# FPGA_BANKS.net
KiCad netlist of a schematic drawn in Altium Designer
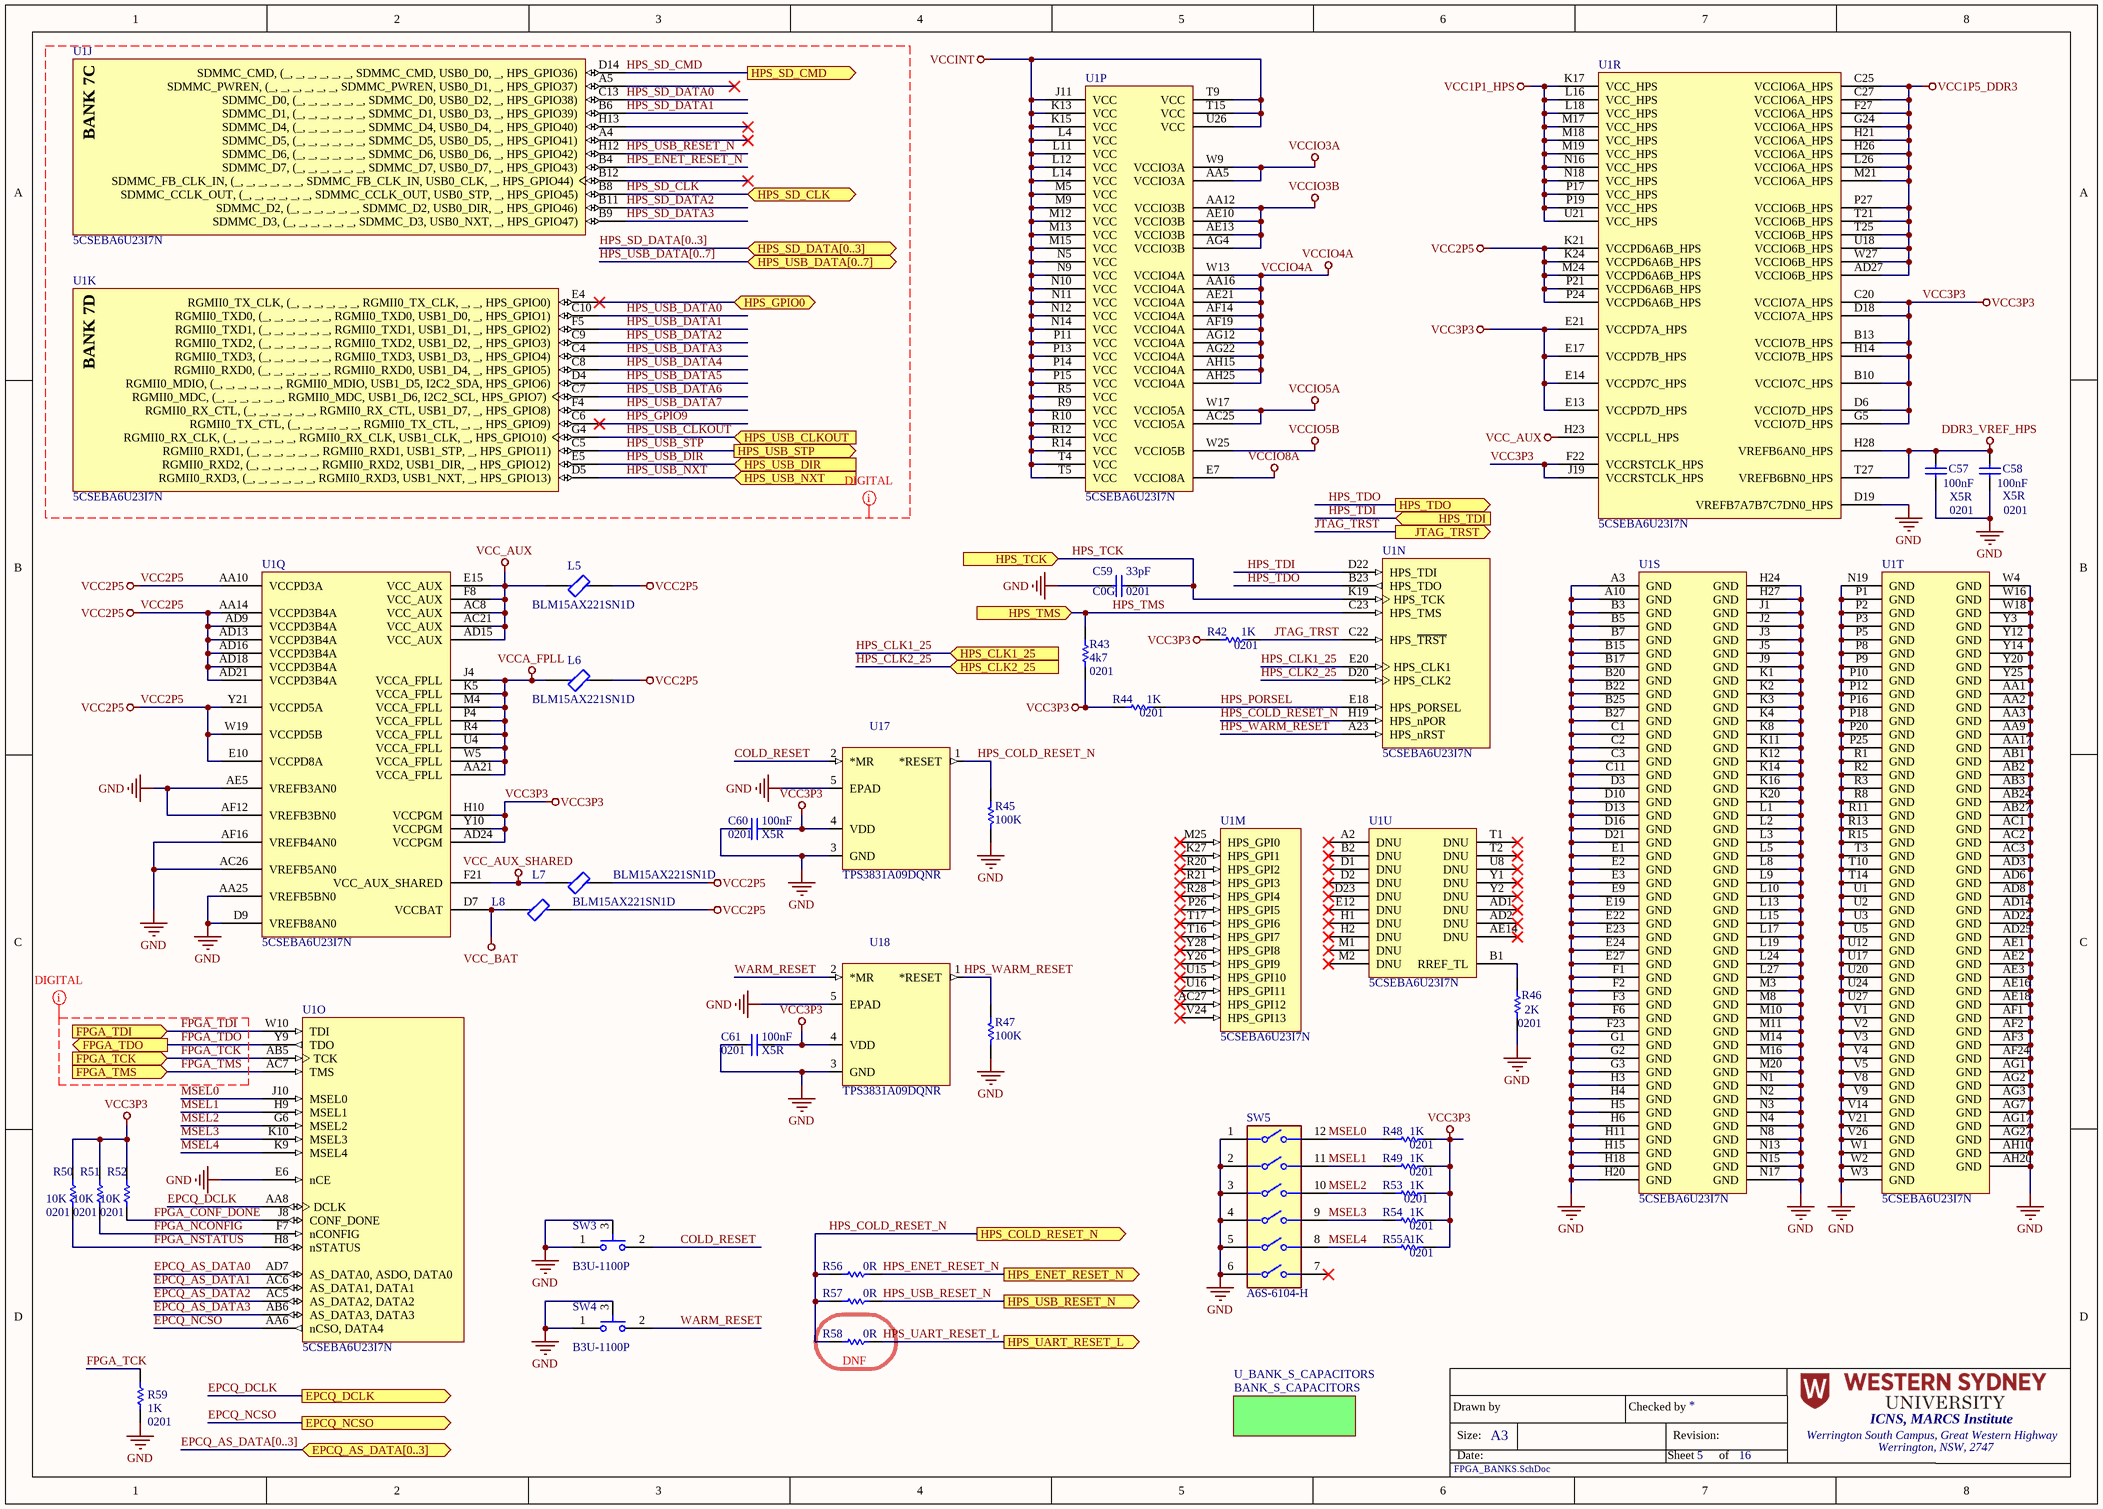
[diagram p0: FPGA_BANKS.SchDoc]

(export (version "E")
  (design (tool "Eeschema 10.0.6"))
  (components
    (comp (ref "C57")
      (value "CL03A104KP3NNNC")
      (footprint "CAP 0201 (0603)")
      (description "Cap Ceramic 0.1uF 10V X5R 10% Pad SMD 0201 85C T/R")
      (fields
        (field (name "TOLERANCE") "10%")
        (field (name "CAPACITANCE") "100nF")
        (field (name "MANUFACTURER") "Samsung")
        (field (name "CASE CODE (IMPERIAL)") "0201")
        (field (name "DIELECTRIC") "X5R")
        (field (name "SOURCE") "ICNS_PropheseeLib.SchLib")
      )
      (libsource (lib "Western Sydney University - ICNS") (part "CL03A104KP3NNNC"))
    )
    (comp (ref "C58")
      (value "CL03A104KP3NNNC")
      (footprint "CAP 0201 (0603)")
      (description "Cap Ceramic 0.1uF 10V X5R 10% Pad SMD 0201 85C T/R")
      (fields
        (field (name "TOLERANCE") "10%")
        (field (name "CAPACITANCE") "100nF")
        (field (name "MANUFACTURER") "Samsung")
        (field (name "CASE CODE (IMPERIAL)") "0201")
        (field (name "DIELECTRIC") "X5R")
        (field (name "SOURCE") "ICNS_PropheseeLib.SchLib")
      )
      (libsource (lib "Western Sydney University - ICNS") (part "CL03A104KP3NNNC"))
    )
    (comp (ref "C59")
      (value "CGA1A2C0G1E330J030BA")
      (footprint "CAP 0201 (0603)")
      (description "Cap Ceramic 33 pF 25V ±5% C0G, NP0 0201 (0603 Metric)")
      (fields
        (field (name "TOLERANCE") "5%")
        (field (name "MANUFACTURER") "TDK")
        (field (name "CAPACITANCE") "33pF")
        (field (name "CASE CODE (IMPERIAL)") "0201")
        (field (name "DIELECTRIC") "C0G")
        (field (name "SOURCE") "ICNS_PropheseeLib.SchLib")
      )
      (libsource (lib "Western Sydney University - ICNS") (part "CGA1A2C0G1E330J030BA"))
    )
    (comp (ref "C60")
      (value "CL03A104KP3NNNC")
      (footprint "CAP 0201 (0603)")
      (description "Cap Ceramic 0.1uF 10V X5R 10% Pad SMD 0201 85C T/R")
      (fields
        (field (name "TOLERANCE") "10%")
        (field (name "CAPACITANCE") "100nF")
        (field (name "MANUFACTURER") "Samsung")
        (field (name "CASE CODE (IMPERIAL)") "0201")
        (field (name "DIELECTRIC") "X5R")
        (field (name "SOURCE") "ICNS_PropheseeLib.SchLib")
      )
      (libsource (lib "Western Sydney University - ICNS") (part "CL03A104KP3NNNC"))
    )
    (comp (ref "C61")
      (value "CL03A104KP3NNNC")
      (footprint "CAP 0201 (0603)")
      (description "Cap Ceramic 0.1uF 10V X5R 10% Pad SMD 0201 85C T/R")
      (fields
        (field (name "TOLERANCE") "10%")
        (field (name "CAPACITANCE") "100nF")
        (field (name "MANUFACTURER") "Samsung")
        (field (name "CASE CODE (IMPERIAL)") "0201")
        (field (name "DIELECTRIC") "X5R")
        (field (name "SOURCE") "ICNS_PropheseeLib.SchLib")
      )
      (libsource (lib "Western Sydney University - ICNS") (part "CL03A104KP3NNNC"))
    )
    (comp (ref "L5")
      (value "BLM15AX221SN1D")
      (footprint "FP-BLM15-0_05-IPC_C")
      (description "Ferrite Bead Multi-Layer 220 Ohms @ 100 MHz 0402 (1005 Metric) 600mA 180mOhm")
      (fields
        (field (name "TOLERANCE") "25%")
        (field (name "MANUFACTURER") "Murata")
        (field (name "SOURCE") "ICNS_PropheseeLib.SchLib")
      )
      (libsource (lib "Western Sydney University - ICNS") (part "BLM15AX221SN1D"))
    )
    (comp (ref "L6")
      (value "BLM15AX221SN1D")
      (footprint "FP-BLM15-0_05-IPC_C")
      (description "Ferrite Bead Multi-Layer 220 Ohms @ 100 MHz 0402 (1005 Metric) 600mA 180mOhm")
      (fields
        (field (name "TOLERANCE") "25%")
        (field (name "MANUFACTURER") "Murata")
        (field (name "SOURCE") "ICNS_PropheseeLib.SchLib")
      )
      (libsource (lib "Western Sydney University - ICNS") (part "BLM15AX221SN1D"))
    )
    (comp (ref "L7")
      (value "BLM15AX221SN1D")
      (footprint "FP-BLM15-0_05-IPC_C")
      (description "Ferrite Bead Multi-Layer 220 Ohms @ 100 MHz 0402 (1005 Metric) 600mA 180mOhm")
      (fields
        (field (name "TOLERANCE") "25%")
        (field (name "MANUFACTURER") "Murata")
        (field (name "SOURCE") "ICNS_PropheseeLib.SchLib")
      )
      (libsource (lib "Western Sydney University - ICNS") (part "BLM15AX221SN1D"))
    )
    (comp (ref "L8")
      (value "BLM15AX221SN1D")
      (footprint "FP-BLM15-0_05-IPC_C")
      (description "Ferrite Bead Multi-Layer 220 Ohms @ 100 MHz 0402 (1005 Metric) 600mA 180mOhm")
      (fields
        (field (name "TOLERANCE") "25%")
        (field (name "MANUFACTURER") "Murata")
        (field (name "SOURCE") "ICNS_PropheseeLib.SchLib")
      )
      (libsource (lib "Western Sydney University - ICNS") (part "BLM15AX221SN1D"))
    )
    (comp (ref "R42")
      (value "1K")
      (footprint "RES 0201 (0603)")
      (description "Res Thick Film 0201 1K Ohm 1% 0.05W(1/20W) ±200ppm/C Pad SMD Automotive T/R")
      (fields
        (field (name "MANUFACTURER") "Yageo")
        (field (name "TOLERANCE") "1%")
        (field (name "CASE CODE (IMPERIAL)") "0201")
        (field (name "SOURCE") "ICNS_PropheseeLib.SchLib")
      )
      (libsource (lib "Western Sydney University - ICNS") (part "Symbol"))
    )
    (comp (ref "R43")
      (value "4k7")
      (footprint "RES 0201 (0603)")
      (description "Res Thick Film 0201 4.7K Ohm 1% 1/20W ±200ppm/°C Molded SMD Paper T/R")
      (fields
        (field (name "MANUFACTURER") "Yageo")
        (field (name "CASE CODE (IMPERIAL)") "0201")
        (field (name "MANUFACTURER PART NUMBER") "AC0201FR-074K7L")
        (field (name "SOURCE") "ICNS_PropheseeLib.SchLib")
      )
      (libsource (lib "Western Sydney University - ICNS") (part "Symbol"))
    )
    (comp (ref "R44")
      (value "1K")
      (footprint "RES 0201 (0603)")
      (description "Res Thick Film 0201 1K Ohm 1% 0.05W(1/20W) ±200ppm/C Pad SMD Automotive T/R")
      (fields
        (field (name "MANUFACTURER") "Yageo")
        (field (name "TOLERANCE") "1%")
        (field (name "CASE CODE (IMPERIAL)") "0201")
        (field (name "SOURCE") "ICNS_PropheseeLib.SchLib")
      )
      (libsource (lib "Western Sydney University - ICNS") (part "Symbol"))
    )
    (comp (ref "R45")
      (value "100K")
      (footprint "RES 0402 (1005)")
      (description "Res Thick Film 0402 100K Ohm 1% 0.2W(1/5W) ±100ppm/C Pad SMD Automotive T/R")
      (fields
        (field (name "TOLERANCE") "1%")
        (field (name "Comment") "CRCW0402100KFKEDHP")
        (field (name "SOURCE") "ICNS_PropheseeLib.SchLib")
      )
      (libsource (lib "Western Sydney University - ICNS") (part "Symbol"))
    )
    (comp (ref "R46")
      (value "2K")
      (footprint "RES 0201 (0603)")
      (description "Res Thick Film 0201 2K Ohm 1% 1/20W ±100ppm/°C Molded SMD SMD Paper T/R")
      (fields
        (field (name "MANUFACTURER") "Vishay Dale")
        (field (name "CASE CODE (IMPERIAL)") "0201")
        (field (name "MANUFACTURER PART NUMBER") "CRCW02012K00FKED")
        (field (name "SOURCE") "ICNS_PropheseeLib.SchLib")
      )
      (libsource (lib "Western Sydney University - ICNS") (part "CRCW02012K00FKED"))
    )
    (comp (ref "R47")
      (value "100K")
      (footprint "RES 0402 (1005)")
      (description "Res Thick Film 0402 100K Ohm 1% 0.2W(1/5W) ±100ppm/C Pad SMD Automotive T/R")
      (fields
        (field (name "TOLERANCE") "1%")
        (field (name "Comment") "CRCW0402100KFKEDHP")
        (field (name "SOURCE") "ICNS_PropheseeLib.SchLib")
      )
      (libsource (lib "Western Sydney University - ICNS") (part "Symbol"))
    )
    (comp (ref "R48")
      (value "1K")
      (footprint "RES 0201 (0603)")
      (description "Res Thick Film 0201 1K Ohm 1% 0.05W(1/20W) ±200ppm/C Pad SMD Automotive T/R")
      (fields
        (field (name "MANUFACTURER") "Yageo")
        (field (name "TOLERANCE") "1%")
        (field (name "CASE CODE (IMPERIAL)") "0201")
        (field (name "SOURCE") "ICNS_PropheseeLib.SchLib")
      )
      (libsource (lib "Western Sydney University - ICNS") (part "Symbol"))
    )
    (comp (ref "R49")
      (value "1K")
      (footprint "RES 0201 (0603)")
      (description "Res Thick Film 0201 1K Ohm 1% 0.05W(1/20W) ±200ppm/C Pad SMD Automotive T/R")
      (fields
        (field (name "MANUFACTURER") "Yageo")
        (field (name "TOLERANCE") "1%")
        (field (name "CASE CODE (IMPERIAL)") "0201")
        (field (name "SOURCE") "ICNS_PropheseeLib.SchLib")
      )
      (libsource (lib "Western Sydney University - ICNS") (part "Symbol"))
    )
    (comp (ref "R50")
      (value "10K")
      (footprint "RES 0201 (0603)")
      (description "Res Thick Film 0201 10K Ohm 1% 0.05W(1/20W) ±200ppm/C Pad SMD Automotive T/R")
      (fields
        (field (name "MANUFACTURER") "Yageo")
        (field (name "MANUFACTURER PART NUMBER") "AC0201FR-0710KL")
        (field (name "CASE CODE (IMPERIAL)") "0201")
        (field (name "SOURCE") "ICNS_PropheseeLib.SchLib")
      )
      (libsource (lib "Western Sydney University - ICNS") (part "Symbol"))
    )
    (comp (ref "R51")
      (value "10K")
      (footprint "RES 0201 (0603)")
      (description "Res Thick Film 0201 10K Ohm 1% 0.05W(1/20W) ±200ppm/C Pad SMD Automotive T/R")
      (fields
        (field (name "MANUFACTURER") "Yageo")
        (field (name "MANUFACTURER PART NUMBER") "AC0201FR-0710KL")
        (field (name "CASE CODE (IMPERIAL)") "0201")
        (field (name "SOURCE") "ICNS_PropheseeLib.SchLib")
      )
      (libsource (lib "Western Sydney University - ICNS") (part "Symbol"))
    )
    (comp (ref "R52")
      (value "10K")
      (footprint "RES 0201 (0603)")
      (description "Res Thick Film 0201 10K Ohm 1% 0.05W(1/20W) ±200ppm/C Pad SMD Automotive T/R")
      (fields
        (field (name "MANUFACTURER") "Yageo")
        (field (name "MANUFACTURER PART NUMBER") "AC0201FR-0710KL")
        (field (name "CASE CODE (IMPERIAL)") "0201")
        (field (name "SOURCE") "ICNS_PropheseeLib.SchLib")
      )
      (libsource (lib "Western Sydney University - ICNS") (part "Symbol"))
    )
    (comp (ref "R53")
      (value "1K")
      (footprint "RES 0201 (0603)")
      (description "Res Thick Film 0201 1K Ohm 1% 0.05W(1/20W) ±200ppm/C Pad SMD Automotive T/R")
      (fields
        (field (name "MANUFACTURER") "Yageo")
        (field (name "TOLERANCE") "1%")
        (field (name "CASE CODE (IMPERIAL)") "0201")
        (field (name "SOURCE") "ICNS_PropheseeLib.SchLib")
      )
      (libsource (lib "Western Sydney University - ICNS") (part "Symbol"))
    )
    (comp (ref "R54")
      (value "1K")
      (footprint "RES 0201 (0603)")
      (description "Res Thick Film 0201 1K Ohm 1% 0.05W(1/20W) ±200ppm/C Pad SMD Automotive T/R")
      (fields
        (field (name "MANUFACTURER") "Yageo")
        (field (name "TOLERANCE") "1%")
        (field (name "CASE CODE (IMPERIAL)") "0201")
        (field (name "SOURCE") "ICNS_PropheseeLib.SchLib")
      )
      (libsource (lib "Western Sydney University - ICNS") (part "Symbol"))
    )
    (comp (ref "R55A")
      (value "1K")
      (footprint "RES 0201 (0603)")
      (description "Res Thick Film 0201 1K Ohm 1% 0.05W(1/20W) ±200ppm/C Pad SMD Automotive T/R")
      (fields
        (field (name "TOLERANCE") "1%")
        (field (name "MANUFACTURER") "Yageo")
        (field (name "CASE CODE (IMPERIAL)") "0201")
        (field (name "SOURCE") "ICNS_PropheseeLib.SchLib")
      )
      (libsource (lib "Western Sydney University - ICNS") (part "Symbol"))
    )
    (comp (ref "R56")
      (value "0R")
      (footprint "RES 0201 (0603)")
      (description "Res Thick Film 0201 0 Ohm Sulfur Resistant Pad SMD Automotive T/R")
      (fields
        (field (name "MANUFACTURER") "Yageo")
        (field (name "MANUFACTURER PART NUMBER") "AF0201JR-070RL")
        (field (name "SOURCE") "ICNS_PropheseeLib.SchLib")
      )
      (libsource (lib "Western Sydney University - ICNS") (part "Symbol"))
    )
    (comp (ref "R57")
      (value "0R")
      (footprint "RES 0201 (0603)")
      (description "Res Thick Film 0201 0 Ohm Sulfur Resistant Pad SMD Automotive T/R")
      (fields
        (field (name "MANUFACTURER") "Yageo")
        (field (name "MANUFACTURER PART NUMBER") "AF0201JR-070RL")
        (field (name "SOURCE") "ICNS_PropheseeLib.SchLib")
      )
      (libsource (lib "Western Sydney University - ICNS") (part "Symbol"))
    )
    (comp (ref "R58")
      (value "0R")
      (footprint "RES 0201 (0603)")
      (description "Res Thick Film 0201 0 Ohm Sulfur Resistant Pad SMD Automotive T/R")
      (fields
        (field (name "MANUFACTURER") "Yageo")
        (field (name "MANUFACTURER PART NUMBER") "AF0201JR-070RL")
        (field (name "SOURCE") "ICNS_PropheseeLib.SchLib")
      )
      (libsource (lib "Western Sydney University - ICNS") (part "Symbol"))
    )
    (comp (ref "R59")
      (value "1K")
      (footprint "RES 0201 (0603)")
      (description "Res Thick Film 0201 1K Ohm 1% 0.05W(1/20W) ±200ppm/C Pad SMD Automotive T/R")
      (fields
        (field (name "MANUFACTURER") "Yageo")
        (field (name "TOLERANCE") "1%")
        (field (name "CASE CODE (IMPERIAL)") "0201")
        (field (name "SOURCE") "ICNS_PropheseeLib.SchLib")
      )
      (libsource (lib "Western Sydney University - ICNS") (part "Symbol"))
    )
    (comp (ref "SW3")
      (value "B3U-1100P")
      (footprint "FP-B3U-1100P-MFG")
      (description "Switch Tactile N.O. SPST Round Button Gull Wing 0.05A 12VDC 1.5N SMD Embossed T/R")
      (fields (field (name "MANUFACTURER") "Omron") (field (name "SOURCE") "ICNS_PropheseeLib.SchLib"))
      (libsource (lib "Western Sydney University - ICNS") (part "B3U-1100P"))
    )
    (comp (ref "SW4")
      (value "B3U-1100P")
      (footprint "FP-B3U-1100P-MFG")
      (description "Switch Tactile N.O. SPST Round Button Gull Wing 0.05A 12VDC 1.5N SMD Embossed T/R")
      (fields (field (name "MANUFACTURER") "Omron") (field (name "SOURCE") "ICNS_PropheseeLib.SchLib"))
      (libsource (lib "Western Sydney University - ICNS") (part "B3U-1100P"))
    )
    (comp (ref "SW5")
      (value "A6S-6104-H")
      (footprint "FP-A6S-6104-H-MFG")
      (description "Switch DIP OFF ON SPST 6 Raised Slide 0.025A 24VDC Gull Wing 1000Cycles 2.54mm SMD Tube")
      (fields (field (name "MANUFACTURER") "Omron") (field (name "SOURCE") "ICNS_PropheseeLib.SchLib"))
      (libsource (lib "Western Sydney University - ICNS") (part "A6S-6104-H"))
    )
    (comp (ref "U1")
      (value "5CSEBA6U23I7N")
      (footprint "ALTR-UBGA672_A-185")
      (fields (field (name "MANUFACTURER") "Altera") (field (name "SOURCE") "ICNS_PropheseeLib.SchLib"))
      (libsource (lib "Western Sydney University - ICNS") (part "5CSEBA6U23I7N"))
    )
    (comp (ref "U17")
      (value "TPS3831A09DQNR")
      (footprint "DQN0004A_TEX")
      (description "Volt Supervisor Supply Voltage Supervisory 0.914V 6.5V 4-Pin X2SON T/R")
      (fields
        (field (name "MANUFACTURER PART NUMBER") "TPS3831A09DQNR")
        (field (name "MANUFACTURER") "Texas Instruments")
        (field (name "SOURCE") "ICNS_PropheseeLib.SchLib")
      )
      (libsource (lib "Western Sydney University - ICNS") (part "TPS3831A09DQNR"))
    )
    (comp (ref "U18")
      (value "TPS3831A09DQNR")
      (footprint "DQN0004A_TEX")
      (description "Volt Supervisor Supply Voltage Supervisory 0.914V 6.5V 4-Pin X2SON T/R")
      (fields
        (field (name "MANUFACTURER PART NUMBER") "TPS3831A09DQNR")
        (field (name "MANUFACTURER") "Texas Instruments")
        (field (name "SOURCE") "ICNS_PropheseeLib.SchLib")
      )
      (libsource (lib "Western Sydney University - ICNS") (part "TPS3831A09DQNR"))
    )
  )
  (nets
    (net (code "1") (name "/COLD_RESET") (class "Default")
      (node (ref "SW3") (pin "2") (pinfunction "2_2") (pintype "passive"))
      (node (ref "U17") (pin "2") (pinfunction "*MR_2") (pintype "input"))
    )
    (net (code "2") (name "/EPCQ_AS_DATA0") (class "Default")
      (node (ref "U1") (pin "AD7") (pinfunction "AS_DATA0,_ASDO,_DATA0_AD7") (pintype "bidirectional"))
    )
    (net (code "3") (name "/EPCQ_AS_DATA1") (class "Default")
      (node (ref "U1") (pin "AC6") (pinfunction "AS_DATA1,_DATA1_AC6") (pintype "bidirectional"))
    )
    (net (code "4") (name "/EPCQ_AS_DATA2") (class "Default")
      (node (ref "U1") (pin "AC5") (pinfunction "AS_DATA2,_DATA2_AC5") (pintype "bidirectional"))
    )
    (net (code "5") (name "/EPCQ_AS_DATA3") (class "Default")
      (node (ref "U1") (pin "AB6") (pinfunction "AS_DATA3,_DATA3_AB6") (pintype "bidirectional"))
    )
    (net (code "7") (name "/EPCQ_DCLK") (class "Default")
      (node (ref "U1") (pin "AA8") (pinfunction "DCLK_AA8") (pintype "bidirectional"))
    )
    (net (code "8") (name "/EPCQ_NCSO") (class "Default")
      (node (ref "U1") (pin "AA6") (pinfunction "nCSO,_DATA4_AA6") (pintype "output"))
    )
    (net (code "9") (name "/FPGA_CONF_DONE") (class "Default")
      (node (ref "R52") (pin "1") (pinfunction "1_1") (pintype "passive"))
      (node (ref "U1") (pin "J8") (pinfunction "CONF_DONE_J8") (pintype "bidirectional"))
    )
    (net (code "10") (name "/FPGA_NCONFIG") (class "Default")
      (node (ref "R51") (pin "1") (pinfunction "1_1") (pintype "passive"))
      (node (ref "U1") (pin "F7") (pinfunction "nCONFIG_F7") (pintype "input"))
    )
    (net (code "11") (name "/FPGA_NSTATUS") (class "Default")
      (node (ref "R50") (pin "1") (pinfunction "1_1") (pintype "passive"))
      (node (ref "U1") (pin "H8") (pinfunction "nSTATUS_H8") (pintype "bidirectional"))
    )
    (net (code "12") (name "/FPGA_TCK") (class "Default")
      (node (ref "R59") (pin "1") (pinfunction "1_1") (pintype "passive"))
      (node (ref "U1") (pin "AB5") (pinfunction "TCK_AB5") (pintype "input"))
    )
    (net (code "13") (name "/FPGA_TDI") (class "Default")
      (node (ref "U1") (pin "W10") (pinfunction "TDI_W10") (pintype "input"))
    )
    (net (code "14") (name "/FPGA_TDO") (class "Default")
      (node (ref "U1") (pin "Y9") (pinfunction "TDO_Y9") (pintype "output"))
    )
    (net (code "15") (name "/FPGA_TMS") (class "Default")
      (node (ref "U1") (pin "AC7") (pinfunction "TMS_AC7") (pintype "input"))
    )
    (net (code "16") (name "/HPS_CLK1_25") (class "Default")
      (node (ref "U1") (pin "E20") (pinfunction "HPS_CLK1_E20") (pintype "input"))
    )
    (net (code "17") (name "/HPS_CLK2_25") (class "Default")
      (node (ref "U1") (pin "D20") (pinfunction "HPS_CLK2_D20") (pintype "input"))
    )
    (net (code "18") (name "/HPS_COLD_RESET_N") (class "Default")
      (node (ref "R45") (pin "2") (pinfunction "2_2") (pintype "passive"))
      (node (ref "R56") (pin "1") (pinfunction "1_1") (pintype "passive"))
      (node (ref "R57") (pin "1") (pinfunction "1_1") (pintype "passive"))
      (node (ref "R58") (pin "1") (pinfunction "1_1") (pintype "passive"))
      (node (ref "U1") (pin "H19") (pinfunction "HPS_nPOR_H19") (pintype "input"))
      (node (ref "U17") (pin "1") (pinfunction "*RESET_1") (pintype "output"))
    )
    (net (code "19") (name "/HPS_ENET_RESET_N") (class "Default")
      (node (ref "R56") (pin "2") (pinfunction "2_2") (pintype "passive"))
      (node (ref "U1") (pin "B4") (pinfunction "SDMMC_D7,_(_,__,__,__,__,__,_SDMMC_D7,_USB0_D7,__,_HPS_GPIO43)_B4") (pintype "bidirectional"))
    )
    (net (code "20") (name "/HPS_GPIO0") (class "Default")
      (node (ref "U1") (pin "E4") (pinfunction "RGMII0_TX_CLK,_(_,__,__,__,__,__,_RGMII0_TX_CLK,__,__,_HPS_GPIO0)_E4") (pintype "bidirectional+no_connect"))
    )
    (net (code "21") (name "/HPS_GPIO9") (class "Default")
      (node (ref "U1") (pin "C6") (pinfunction "RGMII0_TX_CTL,_(_,__,__,__,__,__,_RGMII0_TX_CTL,__,__,_HPS_GPIO9)_C6") (pintype "bidirectional+no_connect"))
    )
    (net (code "22") (name "/HPS_PORSEL") (class "Default")
      (node (ref "R44") (pin "2") (pinfunction "2_2") (pintype "passive"))
      (node (ref "U1") (pin "E18") (pinfunction "HPS_PORSEL_E18") (pintype "input"))
    )
    (net (code "23") (name "/HPS_SD_CLK") (class "Default")
      (node (ref "U1") (pin "B8") (pinfunction "SDMMC_CCLK_OUT,_(_,__,__,__,__,__,_SDMMC_CCLK_OUT,_USB0_STP,__,_HPS_GPIO45)_B8") (pintype "bidirectional"))
    )
    (net (code "24") (name "/HPS_SD_CMD") (class "Default")
      (node (ref "U1") (pin "D14") (pinfunction "SDMMC_CMD,_(_,__,__,__,__,__,_SDMMC_CMD,_USB0_D0,__,_HPS_GPIO36)_D14") (pintype "bidirectional"))
    )
    (net (code "25") (name "/HPS_SD_DATA0") (class "Default")
      (node (ref "U1") (pin "C13") (pinfunction "SDMMC_D0,_(_,__,__,__,__,__,_SDMMC_D0,_USB0_D2,__,_HPS_GPIO38)_C13") (pintype "bidirectional"))
    )
    (net (code "26") (name "/HPS_SD_DATA1") (class "Default")
      (node (ref "U1") (pin "B6") (pinfunction "SDMMC_D1,_(_,__,__,__,__,__,_SDMMC_D1,_USB0_D3,__,_HPS_GPIO39)_B6") (pintype "bidirectional"))
    )
    (net (code "27") (name "/HPS_SD_DATA2") (class "Default")
      (node (ref "U1") (pin "B11") (pinfunction "SDMMC_D2,_(_,__,__,__,__,__,_SDMMC_D2,_USB0_DIR,__,_HPS_GPIO46)_B11") (pintype "bidirectional"))
    )
    (net (code "28") (name "/HPS_SD_DATA3") (class "Default")
      (node (ref "U1") (pin "B9") (pinfunction "SDMMC_D3,_(_,__,__,__,__,__,_SDMMC_D3,_USB0_NXT,__,_HPS_GPIO47)_B9") (pintype "bidirectional"))
    )
    (net (code "30") (name "/HPS_TCK") (class "Default")
      (node (ref "C59") (pin "1") (pinfunction "1_1") (pintype "passive"))
      (node (ref "U1") (pin "K19") (pinfunction "HPS_TCK_K19") (pintype "input"))
    )
    (net (code "31") (name "/HPS_TDI") (class "Default")
      (node (ref "U1") (pin "D22") (pinfunction "HPS_TDI_D22") (pintype "input"))
    )
    (net (code "32") (name "/HPS_TDO") (class "Default")
      (node (ref "U1") (pin "B23") (pinfunction "HPS_TDO_B23") (pintype "output"))
    )
    (net (code "33") (name "/HPS_TMS") (class "Default")
      (node (ref "R43") (pin "1") (pinfunction "1_1") (pintype "passive"))
      (node (ref "U1") (pin "C23") (pinfunction "HPS_TMS_C23") (pintype "input"))
    )
    (net (code "34") (name "/HPS_UART_RESET_L") (class "Default")
      (node (ref "R58") (pin "2") (pinfunction "2_2") (pintype "passive"))
    )
    (net (code "35") (name "/HPS_USB_CLKOUT") (class "Default")
      (node (ref "U1") (pin "G4") (pinfunction "RGMII0_RX_CLK,_(_,__,__,__,__,__,_RGMII0_RX_CLK,_USB1_CLK,__,_HPS_GPIO10)_G4") (pintype "bidirectional"))
    )
    (net (code "36") (name "/HPS_USB_DATA0") (class "Default")
      (node (ref "U1") (pin "C10") (pinfunction "RGMII0_TXD0,_(_,__,__,__,__,__,_RGMII0_TXD0,_USB1_D0,__,_HPS_GPIO1)_C10") (pintype "bidirectional"))
    )
    (net (code "37") (name "/HPS_USB_DATA1") (class "Default")
      (node (ref "U1") (pin "F5") (pinfunction "RGMII0_TXD1,_(_,__,__,__,__,__,_RGMII0_TXD1,_USB1_D1,__,_HPS_GPIO2)_F5") (pintype "bidirectional"))
    )
    (net (code "38") (name "/HPS_USB_DATA2") (class "Default")
      (node (ref "U1") (pin "C9") (pinfunction "RGMII0_TXD2,_(_,__,__,__,__,__,_RGMII0_TXD2,_USB1_D2,__,_HPS_GPIO3)_C9") (pintype "bidirectional"))
    )
    (net (code "39") (name "/HPS_USB_DATA3") (class "Default")
      (node (ref "U1") (pin "C4") (pinfunction "RGMII0_TXD3,_(_,__,__,__,__,__,_RGMII0_TXD3,_USB1_D3,__,_HPS_GPIO4)_C4") (pintype "bidirectional"))
    )
    (net (code "40") (name "/HPS_USB_DATA4") (class "Default")
      (node (ref "U1") (pin "C8") (pinfunction "RGMII0_RXD0,_(_,__,__,__,__,__,_RGMII0_RXD0,_USB1_D4,__,_HPS_GPIO5)_C8") (pintype "bidirectional"))
    )
    (net (code "41") (name "/HPS_USB_DATA5") (class "Default")
      (node (ref "U1") (pin "D4") (pinfunction "RGMII0_MDIO,_(_,__,__,__,__,__,_RGMII0_MDIO,_USB1_D5,_I2C2_SDA,_HPS_GPIO6)_D4") (pintype "bidirectional"))
    )
    (net (code "42") (name "/HPS_USB_DATA6") (class "Default")
      (node (ref "U1") (pin "C7") (pinfunction "RGMII0_MDC,_(_,__,__,__,__,__,_RGMII0_MDC,_USB1_D6,_I2C2_SCL,_HPS_GPIO7)_C7") (pintype "bidirectional"))
    )
    (net (code "43") (name "/HPS_USB_DATA7") (class "Default")
      (node (ref "U1") (pin "F4") (pinfunction "RGMII0_RX_CTL,_(_,__,__,__,__,__,_RGMII0_RX_CTL,_USB1_D7,__,_HPS_GPIO8)_F4") (pintype "bidirectional"))
    )
    (net (code "45") (name "/HPS_USB_DIR") (class "Default")
      (node (ref "U1") (pin "E5") (pinfunction "RGMII0_RXD2,_(_,__,__,__,__,__,_RGMII0_RXD2,_USB1_DIR,__,_HPS_GPIO12)_E5") (pintype "bidirectional"))
    )
    (net (code "46") (name "/HPS_USB_NXT") (class "Default")
      (node (ref "U1") (pin "D5") (pinfunction "RGMII0_RXD3,_(_,__,__,__,__,__,_RGMII0_RXD3,_USB1_NXT,__,_HPS_GPIO13)_D5") (pintype "bidirectional"))
    )
    (net (code "47") (name "/HPS_USB_RESET_N") (class "Default")
      (node (ref "R57") (pin "2") (pinfunction "2_2") (pintype "passive"))
      (node (ref "U1") (pin "H12") (pinfunction "SDMMC_D6,_(_,__,__,__,__,__,_SDMMC_D6,_USB0_D6,__,_HPS_GPIO42)_H12") (pintype "bidirectional"))
    )
    (net (code "48") (name "/HPS_USB_STP") (class "Default")
      (node (ref "U1") (pin "C5") (pinfunction "RGMII0_RXD1,_(_,__,__,__,__,__,_RGMII0_RXD1,_USB1_STP,__,_HPS_GPIO11)_C5") (pintype "bidirectional"))
    )
    (net (code "49") (name "/HPS_WARM_RESET") (class "Default")
      (node (ref "R47") (pin "2") (pinfunction "2_2") (pintype "passive"))
      (node (ref "U1") (pin "A23") (pinfunction "HPS_nRST_A23") (pintype "input"))
      (node (ref "U18") (pin "1") (pinfunction "*RESET_1") (pintype "output"))
    )
    (net (code "50") (name "/JTAG_TRST") (class "Default")
      (node (ref "R42") (pin "2") (pinfunction "2_2") (pintype "passive"))
      (node (ref "U1") (pin "C22") (pinfunction "HPS_~{TRST}_C22") (pintype "input"))
    )
    (net (code "51") (name "/MSEL0") (class "Default")
      (node (ref "R48") (pin "1") (pinfunction "1_1") (pintype "passive"))
      (node (ref "SW5") (pin "12") (pinfunction "12_12") (pintype "passive"))
      (node (ref "U1") (pin "J10") (pinfunction "MSEL0_J10") (pintype "input"))
    )
    (net (code "52") (name "/MSEL1") (class "Default")
      (node (ref "R49") (pin "1") (pinfunction "1_1") (pintype "passive"))
      (node (ref "SW5") (pin "11") (pinfunction "11_11") (pintype "passive"))
      (node (ref "U1") (pin "H9") (pinfunction "MSEL1_H9") (pintype "input"))
    )
    (net (code "53") (name "/MSEL2") (class "Default")
      (node (ref "R53") (pin "1") (pinfunction "1_1") (pintype "passive"))
      (node (ref "SW5") (pin "10") (pinfunction "10_10") (pintype "passive"))
      (node (ref "U1") (pin "G6") (pinfunction "MSEL2_G6") (pintype "input"))
    )
    (net (code "54") (name "/MSEL3") (class "Default")
      (node (ref "R54") (pin "1") (pinfunction "1_1") (pintype "passive"))
      (node (ref "SW5") (pin "9") (pinfunction "9_9") (pintype "passive"))
      (node (ref "U1") (pin "K10") (pinfunction "MSEL3_K10") (pintype "input"))
    )
    (net (code "55") (name "/MSEL4") (class "Default")
      (node (ref "R55A") (pin "1") (pinfunction "1_1") (pintype "passive"))
      (node (ref "SW5") (pin "8") (pinfunction "8_8") (pintype "passive"))
      (node (ref "U1") (pin "K9") (pinfunction "MSEL4_K9") (pintype "input"))
    )
    (net (code "56") (name "/WARM_RESET") (class "Default")
      (node (ref "SW4") (pin "2") (pinfunction "2_2") (pintype "passive"))
      (node (ref "U18") (pin "2") (pinfunction "*MR_2") (pintype "input"))
    )
    (net (code "57") (name "DDR3_VREF_HPS") (class "Default")
      (node (ref "C57") (pin "2") (pinfunction "2_2") (pintype "passive"))
      (node (ref "C58") (pin "2") (pinfunction "2_2") (pintype "passive"))
      (node (ref "U1") (pin "H28") (pinfunction "VREFB6AN0_HPS_H28") (pintype "power_in"))
      (node (ref "U1") (pin "T27") (pinfunction "VREFB6BN0_HPS_T27") (pintype "power_in"))
    )
    (net (code "58") (name "GND") (class "Default")
      (node (ref "C57") (pin "1") (pinfunction "1_1") (pintype "passive"))
      (node (ref "C58") (pin "1") (pinfunction "1_1") (pintype "passive"))
      (node (ref "C59") (pin "2") (pinfunction "2_2") (pintype "passive"))
      (node (ref "C60") (pin "1") (pinfunction "1_1") (pintype "passive"))
      (node (ref "C61") (pin "1") (pinfunction "1_1") (pintype "passive"))
      (node (ref "R45") (pin "1") (pinfunction "1_1") (pintype "passive"))
      (node (ref "R46") (pin "2") (pinfunction "2_2") (pintype "passive"))
      (node (ref "R47") (pin "1") (pinfunction "1_1") (pintype "passive"))
      (node (ref "R59") (pin "2") (pinfunction "2_2") (pintype "passive"))
      (node (ref "SW3") (pin "1") (pinfunction "1_1") (pintype "passive"))
      (node (ref "SW3") (pin "3") (pinfunction "3_3") (pintype "passive"))
      (node (ref "SW4") (pin "1") (pinfunction "1_1") (pintype "passive"))
      (node (ref "SW4") (pin "3") (pinfunction "3_3") (pintype "passive"))
      (node (ref "SW5") (pin "1") (pinfunction "1_1") (pintype "passive"))
      (node (ref "SW5") (pin "2") (pinfunction "2_2") (pintype "passive"))
      (node (ref "SW5") (pin "3") (pinfunction "3_3") (pintype "passive"))
      (node (ref "SW5") (pin "4") (pinfunction "4_4") (pintype "passive"))
      (node (ref "SW5") (pin "5") (pinfunction "5_5") (pintype "passive"))
      (node (ref "SW5") (pin "6") (pinfunction "6_6") (pintype "passive"))
      (node (ref "U1") (pin "A10") (pinfunction "GND_A10") (pintype "power_in"))
      (node (ref "U1") (pin "A3") (pinfunction "GND_A3") (pintype "power_in"))
      (node (ref "U1") (pin "AA1") (pinfunction "GND_AA1") (pintype "power_in"))
      (node (ref "U1") (pin "AA17") (pinfunction "GND_AA17") (pintype "power_in"))
      (node (ref "U1") (pin "AA2") (pinfunction "GND_AA2") (pintype "power_in"))
      (node (ref "U1") (pin "AA25") (pinfunction "VREFB5BN0_AA25") (pintype "power_in"))
      (node (ref "U1") (pin "AA3") (pinfunction "GND_AA3") (pintype "power_in"))
      (node (ref "U1") (pin "AA9") (pinfunction "GND_AA9") (pintype "power_in"))
      (node (ref "U1") (pin "AB1") (pinfunction "GND_AB1") (pintype "power_in"))
      (node (ref "U1") (pin "AB2") (pinfunction "GND_AB2") (pintype "power_in"))
      (node (ref "U1") (pin "AB24") (pinfunction "GND_AB24") (pintype "power_in"))
      (node (ref "U1") (pin "AB27") (pinfunction "GND_AB27") (pintype "power_in"))
      (node (ref "U1") (pin "AB3") (pinfunction "GND_AB3") (pintype "power_in"))
      (node (ref "U1") (pin "AC1") (pinfunction "GND_AC1") (pintype "power_in"))
      (node (ref "U1") (pin "AC2") (pinfunction "GND_AC2") (pintype "power_in"))
      (node (ref "U1") (pin "AC26") (pinfunction "VREFB5AN0_AC26") (pintype "power_in"))
      (node (ref "U1") (pin "AC3") (pinfunction "GND_AC3") (pintype "power_in"))
      (node (ref "U1") (pin "AD14") (pinfunction "GND_AD14") (pintype "power_in"))
      (node (ref "U1") (pin "AD22") (pinfunction "GND_AD22") (pintype "power_in"))
      (node (ref "U1") (pin "AD25") (pinfunction "GND_AD25") (pintype "power_in"))
      (node (ref "U1") (pin "AD3") (pinfunction "GND_AD3") (pintype "power_in"))
      (node (ref "U1") (pin "AD6") (pinfunction "GND_AD6") (pintype "power_in"))
      (node (ref "U1") (pin "AD8") (pinfunction "GND_AD8") (pintype "power_in"))
      (node (ref "U1") (pin "AE1") (pinfunction "GND_AE1") (pintype "power_in"))
      (node (ref "U1") (pin "AE16") (pinfunction "GND_AE16") (pintype "power_in"))
      (node (ref "U1") (pin "AE18") (pinfunction "GND_AE18") (pintype "power_in"))
      (node (ref "U1") (pin "AE2") (pinfunction "GND_AE2") (pintype "power_in"))
      (node (ref "U1") (pin "AE3") (pinfunction "GND_AE3") (pintype "power_in"))
      (node (ref "U1") (pin "AE5") (pinfunction "VREFB3AN0_AE5") (pintype "power_in"))
      (node (ref "U1") (pin "AF1") (pinfunction "GND_AF1") (pintype "power_in"))
      (node (ref "U1") (pin "AF12") (pinfunction "VREFB3BN0_AF12") (pintype "power_in"))
      (node (ref "U1") (pin "AF16") (pinfunction "VREFB4AN0_AF16") (pintype "power_in"))
      (node (ref "U1") (pin "AF2") (pinfunction "GND_AF2") (pintype "power_in"))
      (node (ref "U1") (pin "AF24") (pinfunction "GND_AF24") (pintype "power_in"))
      (node (ref "U1") (pin "AF3") (pinfunction "GND_AF3") (pintype "power_in"))
      (node (ref "U1") (pin "AG1") (pinfunction "GND_AG1") (pintype "power_in"))
      (node (ref "U1") (pin "AG17") (pinfunction "GND_AG17") (pintype "power_in"))
      (node (ref "U1") (pin "AG2") (pinfunction "GND_AG2") (pintype "power_in"))
      (node (ref "U1") (pin "AG27") (pinfunction "GND_AG27") (pintype "power_in"))
      (node (ref "U1") (pin "AG3") (pinfunction "GND_AG3") (pintype "power_in"))
      (node (ref "U1") (pin "AG7") (pinfunction "GND_AG7") (pintype "power_in"))
      (node (ref "U1") (pin "AH10") (pinfunction "GND_AH10") (pintype "power_in"))
      (node (ref "U1") (pin "AH20") (pinfunction "GND_AH20") (pintype "power_in"))
      (node (ref "U1") (pin "B15") (pinfunction "GND_B15") (pintype "power_in"))
      (node (ref "U1") (pin "B17") (pinfunction "GND_B17") (pintype "power_in"))
      (node (ref "U1") (pin "B20") (pinfunction "GND_B20") (pintype "power_in"))
      (node (ref "U1") (pin "B22") (pinfunction "GND_B22") (pintype "power_in"))
      (node (ref "U1") (pin "B25") (pinfunction "GND_B25") (pintype "power_in"))
      (node (ref "U1") (pin "B27") (pinfunction "GND_B27") (pintype "power_in"))
      (node (ref "U1") (pin "B3") (pinfunction "GND_B3") (pintype "power_in"))
      (node (ref "U1") (pin "B5") (pinfunction "GND_B5") (pintype "power_in"))
      (node (ref "U1") (pin "B7") (pinfunction "GND_B7") (pintype "power_in"))
      (node (ref "U1") (pin "C1") (pinfunction "GND_C1") (pintype "power_in"))
      (node (ref "U1") (pin "C11") (pinfunction "GND_C11") (pintype "power_in"))
      (node (ref "U1") (pin "C2") (pinfunction "GND_C2") (pintype "power_in"))
      (node (ref "U1") (pin "C3") (pinfunction "GND_C3") (pintype "power_in"))
      (node (ref "U1") (pin "D10") (pinfunction "GND_D10") (pintype "power_in"))
      (node (ref "U1") (pin "D13") (pinfunction "GND_D13") (pintype "power_in"))
      (node (ref "U1") (pin "D16") (pinfunction "GND_D16") (pintype "power_in"))
      (node (ref "U1") (pin "D19") (pinfunction "VREFB7A7B7C7DN0_HPS_D19") (pintype "power_in"))
      (node (ref "U1") (pin "D21") (pinfunction "GND_D21") (pintype "power_in"))
      (node (ref "U1") (pin "D3") (pinfunction "GND_D3") (pintype "power_in"))
      (node (ref "U1") (pin "D9") (pinfunction "VREFB8AN0_D9") (pintype "power_in"))
      (node (ref "U1") (pin "E1") (pinfunction "GND_E1") (pintype "power_in"))
      (node (ref "U1") (pin "E19") (pinfunction "GND_E19") (pintype "power_in"))
      (node (ref "U1") (pin "E2") (pinfunction "GND_E2") (pintype "power_in"))
      (node (ref "U1") (pin "E22") (pinfunction "GND_E22") (pintype "power_in"))
      (node (ref "U1") (pin "E23") (pinfunction "GND_E23") (pintype "power_in"))
      (node (ref "U1") (pin "E24") (pinfunction "GND_E24") (pintype "power_in"))
      (node (ref "U1") (pin "E27") (pinfunction "GND_E27") (pintype "power_in"))
      (node (ref "U1") (pin "E3") (pinfunction "GND_E3") (pintype "power_in"))
      (node (ref "U1") (pin "E6") (pinfunction "nCE_E6") (pintype "input"))
      (node (ref "U1") (pin "E9") (pinfunction "GND_E9") (pintype "power_in"))
      (node (ref "U1") (pin "F1") (pinfunction "GND_F1") (pintype "power_in"))
      (node (ref "U1") (pin "F2") (pinfunction "GND_F2") (pintype "power_in"))
      (node (ref "U1") (pin "F23") (pinfunction "GND_F23") (pintype "power_in"))
      (node (ref "U1") (pin "F3") (pinfunction "GND_F3") (pintype "power_in"))
      (node (ref "U1") (pin "F6") (pinfunction "GND_F6") (pintype "power_in"))
      (node (ref "U1") (pin "G1") (pinfunction "GND_G1") (pintype "power_in"))
      (node (ref "U1") (pin "G2") (pinfunction "GND_G2") (pintype "power_in"))
      (node (ref "U1") (pin "G3") (pinfunction "GND_G3") (pintype "power_in"))
      (node (ref "U1") (pin "H11") (pinfunction "GND_H11") (pintype "power_in"))
      (node (ref "U1") (pin "H15") (pinfunction "GND_H15") (pintype "power_in"))
      (node (ref "U1") (pin "H18") (pinfunction "GND_H18") (pintype "power_in"))
      (node (ref "U1") (pin "H20") (pinfunction "GND_H20") (pintype "power_in"))
      (node (ref "U1") (pin "H24") (pinfunction "GND_H24") (pintype "power_in"))
      (node (ref "U1") (pin "H27") (pinfunction "GND_H27") (pintype "power_in"))
      (node (ref "U1") (pin "H3") (pinfunction "GND_H3") (pintype "power_in"))
      (node (ref "U1") (pin "H4") (pinfunction "GND_H4") (pintype "power_in"))
      (node (ref "U1") (pin "H5") (pinfunction "GND_H5") (pintype "power_in"))
      (node (ref "U1") (pin "H6") (pinfunction "GND_H6") (pintype "power_in"))
      (node (ref "U1") (pin "J1") (pinfunction "GND_J1") (pintype "power_in"))
      (node (ref "U1") (pin "J2") (pinfunction "GND_J2") (pintype "power_in"))
      (node (ref "U1") (pin "J3") (pinfunction "GND_J3") (pintype "power_in"))
      (node (ref "U1") (pin "J5") (pinfunction "GND_J5") (pintype "power_in"))
      (node (ref "U1") (pin "J9") (pinfunction "GND_J9") (pintype "power_in"))
      (node (ref "U1") (pin "K1") (pinfunction "GND_K1") (pintype "power_in"))
      (node (ref "U1") (pin "K11") (pinfunction "GND_K11") (pintype "power_in"))
      (node (ref "U1") (pin "K12") (pinfunction "GND_K12") (pintype "power_in"))
      (node (ref "U1") (pin "K14") (pinfunction "GND_K14") (pintype "power_in"))
      (node (ref "U1") (pin "K16") (pinfunction "GND_K16") (pintype "power_in"))
      (node (ref "U1") (pin "K2") (pinfunction "GND_K2") (pintype "power_in"))
      (node (ref "U1") (pin "K20") (pinfunction "GND_K20") (pintype "power_in"))
      (node (ref "U1") (pin "K3") (pinfunction "GND_K3") (pintype "power_in"))
      (node (ref "U1") (pin "K4") (pinfunction "GND_K4") (pintype "power_in"))
      (node (ref "U1") (pin "K8") (pinfunction "GND_K8") (pintype "power_in"))
      (node (ref "U1") (pin "L1") (pinfunction "GND_L1") (pintype "power_in"))
      (node (ref "U1") (pin "L10") (pinfunction "GND_L10") (pintype "power_in"))
      (node (ref "U1") (pin "L13") (pinfunction "GND_L13") (pintype "power_in"))
      (node (ref "U1") (pin "L15") (pinfunction "GND_L15") (pintype "power_in"))
      (node (ref "U1") (pin "L17") (pinfunction "GND_L17") (pintype "power_in"))
      (node (ref "U1") (pin "L19") (pinfunction "GND_L19") (pintype "power_in"))
      (node (ref "U1") (pin "L2") (pinfunction "GND_L2") (pintype "power_in"))
      (node (ref "U1") (pin "L24") (pinfunction "GND_L24") (pintype "power_in"))
      (node (ref "U1") (pin "L27") (pinfunction "GND_L27") (pintype "power_in"))
      (node (ref "U1") (pin "L3") (pinfunction "GND_L3") (pintype "power_in"))
      (node (ref "U1") (pin "L5") (pinfunction "GND_L5") (pintype "power_in"))
      (node (ref "U1") (pin "L8") (pinfunction "GND_L8") (pintype "power_in"))
      (node (ref "U1") (pin "L9") (pinfunction "GND_L9") (pintype "power_in"))
      (node (ref "U1") (pin "M10") (pinfunction "GND_M10") (pintype "power_in"))
      (node (ref "U1") (pin "M11") (pinfunction "GND_M11") (pintype "power_in"))
      (node (ref "U1") (pin "M14") (pinfunction "GND_M14") (pintype "power_in"))
      (node (ref "U1") (pin "M16") (pinfunction "GND_M16") (pintype "power_in"))
      (node (ref "U1") (pin "M20") (pinfunction "GND_M20") (pintype "power_in"))
      (node (ref "U1") (pin "M3") (pinfunction "GND_M3") (pintype "power_in"))
      (node (ref "U1") (pin "M8") (pinfunction "GND_M8") (pintype "power_in"))
      (node (ref "U1") (pin "N1") (pinfunction "GND_N1") (pintype "power_in"))
      (node (ref "U1") (pin "N13") (pinfunction "GND_N13") (pintype "power_in"))
      (node (ref "U1") (pin "N15") (pinfunction "GND_N15") (pintype "power_in"))
      (node (ref "U1") (pin "N17") (pinfunction "GND_N17") (pintype "power_in"))
      (node (ref "U1") (pin "N19") (pinfunction "GND_N19") (pintype "power_in"))
      (node (ref "U1") (pin "N2") (pinfunction "GND_N2") (pintype "power_in"))
      (node (ref "U1") (pin "N3") (pinfunction "GND_N3") (pintype "power_in"))
      (node (ref "U1") (pin "N4") (pinfunction "GND_N4") (pintype "power_in"))
      (node (ref "U1") (pin "N8") (pinfunction "GND_N8") (pintype "power_in"))
      (node (ref "U1") (pin "P1") (pinfunction "GND_P1") (pintype "power_in"))
      (node (ref "U1") (pin "P10") (pinfunction "GND_P10") (pintype "power_in"))
      (node (ref "U1") (pin "P12") (pinfunction "GND_P12") (pintype "power_in"))
      (node (ref "U1") (pin "P16") (pinfunction "GND_P16") (pintype "power_in"))
      (node (ref "U1") (pin "P18") (pinfunction "GND_P18") (pintype "power_in"))
      (node (ref "U1") (pin "P2") (pinfunction "GND_P2") (pintype "power_in"))
      (node (ref "U1") (pin "P20") (pinfunction "GND_P20") (pintype "power_in"))
      (node (ref "U1") (pin "P25") (pinfunction "GND_P25") (pintype "power_in"))
      (node (ref "U1") (pin "P3") (pinfunction "GND_P3") (pintype "power_in"))
      (node (ref "U1") (pin "P5") (pinfunction "GND_P5") (pintype "power_in"))
      (node (ref "U1") (pin "P8") (pinfunction "GND_P8") (pintype "power_in"))
      (node (ref "U1") (pin "P9") (pinfunction "GND_P9") (pintype "power_in"))
      (node (ref "U1") (pin "R1") (pinfunction "GND_R1") (pintype "power_in"))
      (node (ref "U1") (pin "R11") (pinfunction "GND_R11") (pintype "power_in"))
      (node (ref "U1") (pin "R13") (pinfunction "GND_R13") (pintype "power_in"))
      (node (ref "U1") (pin "R15") (pinfunction "GND_R15") (pintype "power_in"))
      (node (ref "U1") (pin "R2") (pinfunction "GND_R2") (pintype "power_in"))
      (node (ref "U1") (pin "R3") (pinfunction "GND_R3") (pintype "power_in"))
      (node (ref "U1") (pin "R8") (pinfunction "GND_R8") (pintype "power_in"))
      (node (ref "U1") (pin "T10") (pinfunction "GND_T10") (pintype "power_in"))
      (node (ref "U1") (pin "T14") (pinfunction "GND_T14") (pintype "power_in"))
      (node (ref "U1") (pin "T3") (pinfunction "GND_T3") (pintype "power_in"))
      (node (ref "U1") (pin "U1") (pinfunction "GND_U1") (pintype "power_in"))
      (node (ref "U1") (pin "U12") (pinfunction "GND_U12") (pintype "power_in"))
      (node (ref "U1") (pin "U17") (pinfunction "GND_U17") (pintype "power_in"))
      (node (ref "U1") (pin "U2") (pinfunction "GND_U2") (pintype "power_in"))
      (node (ref "U1") (pin "U20") (pinfunction "GND_U20") (pintype "power_in"))
      (node (ref "U1") (pin "U24") (pinfunction "GND_U24") (pintype "power_in"))
      (node (ref "U1") (pin "U27") (pinfunction "GND_U27") (pintype "power_in"))
      (node (ref "U1") (pin "U3") (pinfunction "GND_U3") (pintype "power_in"))
      (node (ref "U1") (pin "U5") (pinfunction "GND_U5") (pintype "power_in"))
      (node (ref "U1") (pin "V1") (pinfunction "GND_V1") (pintype "power_in"))
      (node (ref "U1") (pin "V14") (pinfunction "GND_V14") (pintype "power_in"))
      (node (ref "U1") (pin "V2") (pinfunction "GND_V2") (pintype "power_in"))
      (node (ref "U1") (pin "V21") (pinfunction "GND_V21") (pintype "power_in"))
      (node (ref "U1") (pin "V26") (pinfunction "GND_V26") (pintype "power_in"))
      (node (ref "U1") (pin "V3") (pinfunction "GND_V3") (pintype "power_in"))
      (node (ref "U1") (pin "V4") (pinfunction "GND_V4") (pintype "power_in"))
      (node (ref "U1") (pin "V5") (pinfunction "GND_V5") (pintype "power_in"))
      (node (ref "U1") (pin "V8") (pinfunction "GND_V8") (pintype "power_in"))
      (node (ref "U1") (pin "V9") (pinfunction "GND_V9") (pintype "power_in"))
      (node (ref "U1") (pin "W1") (pinfunction "GND_W1") (pintype "power_in"))
      (node (ref "U1") (pin "W16") (pinfunction "GND_W16") (pintype "power_in"))
      (node (ref "U1") (pin "W18") (pinfunction "GND_W18") (pintype "power_in"))
      (node (ref "U1") (pin "W2") (pinfunction "GND_W2") (pintype "power_in"))
      (node (ref "U1") (pin "W3") (pinfunction "GND_W3") (pintype "power_in"))
      (node (ref "U1") (pin "W4") (pinfunction "GND_W4") (pintype "power_in"))
      (node (ref "U1") (pin "Y12") (pinfunction "GND_Y12") (pintype "power_in"))
      (node (ref "U1") (pin "Y14") (pinfunction "GND_Y14") (pintype "power_in"))
      (node (ref "U1") (pin "Y20") (pinfunction "GND_Y20") (pintype "power_in"))
      (node (ref "U1") (pin "Y25") (pinfunction "GND_Y25") (pintype "power_in"))
      (node (ref "U1") (pin "Y3") (pinfunction "GND_Y3") (pintype "power_in"))
      (node (ref "U17") (pin "3") (pinfunction "GND_3") (pintype "power_in"))
      (node (ref "U17") (pin "5") (pinfunction "EPAD_5") (pintype "passive"))
      (node (ref "U18") (pin "3") (pinfunction "GND_3") (pintype "power_in"))
      (node (ref "U18") (pin "5") (pinfunction "EPAD_5") (pintype "passive"))
    )
    (net (code "59") (name "Net-(U1U-RREF_TL)") (class "Default")
      (node (ref "R46") (pin "1") (pinfunction "1_1") (pintype "passive"))
      (node (ref "U1") (pin "B1") (pinfunction "RREF_TL_B1") (pintype "passive"))
    )
    (net (code "60") (name "VCC1P1_HPS") (class "Default")
      (node (ref "U1") (pin "K17") (pinfunction "VCC_HPS_K17") (pintype "power_in"))
      (node (ref "U1") (pin "L16") (pinfunction "VCC_HPS_L16") (pintype "power_in"))
      (node (ref "U1") (pin "L18") (pinfunction "VCC_HPS_L18") (pintype "power_in"))
      (node (ref "U1") (pin "M17") (pinfunction "VCC_HPS_M17") (pintype "power_in"))
      (node (ref "U1") (pin "M18") (pinfunction "VCC_HPS_M18") (pintype "power_in"))
      (node (ref "U1") (pin "M19") (pinfunction "VCC_HPS_M19") (pintype "power_in"))
      (node (ref "U1") (pin "N16") (pinfunction "VCC_HPS_N16") (pintype "power_in"))
      (node (ref "U1") (pin "N18") (pinfunction "VCC_HPS_N18") (pintype "power_in"))
      (node (ref "U1") (pin "P17") (pinfunction "VCC_HPS_P17") (pintype "power_in"))
      (node (ref "U1") (pin "P19") (pinfunction "VCC_HPS_P19") (pintype "power_in"))
      (node (ref "U1") (pin "U21") (pinfunction "VCC_HPS_U21") (pintype "power_in"))
    )
    (net (code "61") (name "VCC1P5_DDR3") (class "Default")
      (node (ref "U1") (pin "AD27") (pinfunction "VCCIO6B_HPS_AD27") (pintype "power_in"))
      (node (ref "U1") (pin "C25") (pinfunction "VCCIO6A_HPS_C25") (pintype "power_in"))
      (node (ref "U1") (pin "C27") (pinfunction "VCCIO6A_HPS_C27") (pintype "power_in"))
      (node (ref "U1") (pin "F27") (pinfunction "VCCIO6A_HPS_F27") (pintype "power_in"))
      (node (ref "U1") (pin "G24") (pinfunction "VCCIO6A_HPS_G24") (pintype "power_in"))
      (node (ref "U1") (pin "H21") (pinfunction "VCCIO6A_HPS_H21") (pintype "power_in"))
      (node (ref "U1") (pin "H26") (pinfunction "VCCIO6A_HPS_H26") (pintype "power_in"))
      (node (ref "U1") (pin "L26") (pinfunction "VCCIO6A_HPS_L26") (pintype "power_in"))
      (node (ref "U1") (pin "M21") (pinfunction "VCCIO6A_HPS_M21") (pintype "power_in"))
      (node (ref "U1") (pin "P27") (pinfunction "VCCIO6B_HPS_P27") (pintype "power_in"))
      (node (ref "U1") (pin "T21") (pinfunction "VCCIO6B_HPS_T21") (pintype "power_in"))
      (node (ref "U1") (pin "T25") (pinfunction "VCCIO6B_HPS_T25") (pintype "power_in"))
      (node (ref "U1") (pin "U18") (pinfunction "VCCIO6B_HPS_U18") (pintype "power_in"))
      (node (ref "U1") (pin "W27") (pinfunction "VCCIO6B_HPS_W27") (pintype "power_in"))
    )
    (net (code "62") (name "VCC2P5") (class "Default")
      (node (ref "L5") (pin "2") (pinfunction "2_2") (pintype "passive"))
      (node (ref "L6") (pin "2") (pinfunction "2_2") (pintype "passive"))
      (node (ref "L7") (pin "2") (pinfunction "2_2") (pintype "passive"))
      (node (ref "L8") (pin "2") (pinfunction "2_2") (pintype "passive"))
      (node (ref "U1") (pin "AA10") (pinfunction "VCCPD3A_AA10") (pintype "power_in"))
      (node (ref "U1") (pin "AA14") (pinfunction "VCCPD3B4A_AA14") (pintype "power_in"))
      (node (ref "U1") (pin "AD13") (pinfunction "VCCPD3B4A_AD13") (pintype "power_in"))
      (node (ref "U1") (pin "AD16") (pinfunction "VCCPD3B4A_AD16") (pintype "power_in"))
      (node (ref "U1") (pin "AD18") (pinfunction "VCCPD3B4A_AD18") (pintype "power_in"))
      (node (ref "U1") (pin "AD21") (pinfunction "VCCPD3B4A_AD21") (pintype "power_in"))
      (node (ref "U1") (pin "AD9") (pinfunction "VCCPD3B4A_AD9") (pintype "power_in"))
      (node (ref "U1") (pin "E10") (pinfunction "VCCPD8A_E10") (pintype "power_in"))
      (node (ref "U1") (pin "K21") (pinfunction "VCCPD6A6B_HPS_K21") (pintype "power_in"))
      (node (ref "U1") (pin "K24") (pinfunction "VCCPD6A6B_HPS_K24") (pintype "power_in"))
      (node (ref "U1") (pin "M24") (pinfunction "VCCPD6A6B_HPS_M24") (pintype "power_in"))
      (node (ref "U1") (pin "P21") (pinfunction "VCCPD6A6B_HPS_P21") (pintype "power_in"))
      (node (ref "U1") (pin "P24") (pinfunction "VCCPD6A6B_HPS_P24") (pintype "power_in"))
      (node (ref "U1") (pin "W19") (pinfunction "VCCPD5B_W19") (pintype "power_in"))
      (node (ref "U1") (pin "Y21") (pinfunction "VCCPD5A_Y21") (pintype "power_in"))
    )
    (net (code "63") (name "VCC3P3") (class "Default")
      (node (ref "C60") (pin "2") (pinfunction "2_2") (pintype "passive"))
      (node (ref "C61") (pin "2") (pinfunction "2_2") (pintype "passive"))
      (node (ref "R42") (pin "1") (pinfunction "1_1") (pintype "passive"))
      (node (ref "R43") (pin "2") (pinfunction "2_2") (pintype "passive"))
      (node (ref "R44") (pin "1") (pinfunction "1_1") (pintype "passive"))
      (node (ref "R48") (pin "2") (pinfunction "2_2") (pintype "passive"))
      (node (ref "R49") (pin "2") (pinfunction "2_2") (pintype "passive"))
      (node (ref "R50") (pin "2") (pinfunction "2_2") (pintype "passive"))
      (node (ref "R51") (pin "2") (pinfunction "2_2") (pintype "passive"))
      (node (ref "R52") (pin "2") (pinfunction "2_2") (pintype "passive"))
      (node (ref "R53") (pin "2") (pinfunction "2_2") (pintype "passive"))
      (node (ref "R54") (pin "2") (pinfunction "2_2") (pintype "passive"))
      (node (ref "R55A") (pin "2") (pinfunction "2_2") (pintype "passive"))
      (node (ref "U1") (pin "AD24") (pinfunction "VCCPGM_AD24") (pintype "power_in"))
      (node (ref "U1") (pin "B10") (pinfunction "VCCIO7C_HPS_B10") (pintype "power_in"))
      (node (ref "U1") (pin "B13") (pinfunction "VCCIO7B_HPS_B13") (pintype "power_in"))
      (node (ref "U1") (pin "C20") (pinfunction "VCCIO7A_HPS_C20") (pintype "power_in"))
      (node (ref "U1") (pin "D18") (pinfunction "VCCIO7A_HPS_D18") (pintype "power_in"))
      (node (ref "U1") (pin "D6") (pinfunction "VCCIO7D_HPS_D6") (pintype "power_in"))
      (node (ref "U1") (pin "E13") (pinfunction "VCCPD7D_HPS_E13") (pintype "power_in"))
      (node (ref "U1") (pin "E14") (pinfunction "VCCPD7C_HPS_E14") (pintype "power_in"))
      (node (ref "U1") (pin "E17") (pinfunction "VCCPD7B_HPS_E17") (pintype "power_in"))
      (node (ref "U1") (pin "E21") (pinfunction "VCCPD7A_HPS_E21") (pintype "power_in"))
      (node (ref "U1") (pin "F22") (pinfunction "VCCRSTCLK_HPS_F22") (pintype "power_in"))
      (node (ref "U1") (pin "G5") (pinfunction "VCCIO7D_HPS_G5") (pintype "power_in"))
      (node (ref "U1") (pin "H10") (pinfunction "VCCPGM_H10") (pintype "power_in"))
      (node (ref "U1") (pin "H14") (pinfunction "VCCIO7B_HPS_H14") (pintype "power_in"))
      (node (ref "U1") (pin "J19") (pinfunction "VCCRSTCLK_HPS_J19") (pintype "power_in"))
      (node (ref "U1") (pin "Y10") (pinfunction "VCCPGM_Y10") (pintype "power_in"))
      (node (ref "U17") (pin "4") (pinfunction "VDD_4") (pintype "power_in"))
      (node (ref "U18") (pin "4") (pinfunction "VDD_4") (pintype "power_in"))
    )
    (net (code "64") (name "VCCA_FPLL") (class "Default")
      (node (ref "L6") (pin "1") (pinfunction "1_1") (pintype "passive"))
      (node (ref "U1") (pin "AA21") (pinfunction "VCCA_FPLL_AA21") (pintype "power_in"))
      (node (ref "U1") (pin "J4") (pinfunction "VCCA_FPLL_J4") (pintype "power_in"))
      (node (ref "U1") (pin "K5") (pinfunction "VCCA_FPLL_K5") (pintype "power_in"))
      (node (ref "U1") (pin "M4") (pinfunction "VCCA_FPLL_M4") (pintype "power_in"))
      (node (ref "U1") (pin "P4") (pinfunction "VCCA_FPLL_P4") (pintype "power_in"))
      (node (ref "U1") (pin "R4") (pinfunction "VCCA_FPLL_R4") (pintype "power_in"))
      (node (ref "U1") (pin "U4") (pinfunction "VCCA_FPLL_U4") (pintype "power_in"))
      (node (ref "U1") (pin "W5") (pinfunction "VCCA_FPLL_W5") (pintype "power_in"))
    )
    (net (code "65") (name "VCCINT") (class "Default")
      (node (ref "U1") (pin "J11") (pinfunction "VCC_J11") (pintype "power_in"))
      (node (ref "U1") (pin "K13") (pinfunction "VCC_K13") (pintype "power_in"))
      (node (ref "U1") (pin "K15") (pinfunction "VCC_K15") (pintype "power_in"))
      (node (ref "U1") (pin "L11") (pinfunction "VCC_L11") (pintype "power_in"))
      (node (ref "U1") (pin "L12") (pinfunction "VCC_L12") (pintype "power_in"))
      (node (ref "U1") (pin "L14") (pinfunction "VCC_L14") (pintype "power_in"))
      (node (ref "U1") (pin "L4") (pinfunction "VCC_L4") (pintype "power_in"))
      (node (ref "U1") (pin "M12") (pinfunction "VCC_M12") (pintype "power_in"))
      (node (ref "U1") (pin "M13") (pinfunction "VCC_M13") (pintype "power_in"))
      (node (ref "U1") (pin "M15") (pinfunction "VCC_M15") (pintype "power_in"))
      (node (ref "U1") (pin "M5") (pinfunction "VCC_M5") (pintype "power_in"))
      (node (ref "U1") (pin "M9") (pinfunction "VCC_M9") (pintype "power_in"))
      (node (ref "U1") (pin "N10") (pinfunction "VCC_N10") (pintype "power_in"))
      (node (ref "U1") (pin "N11") (pinfunction "VCC_N11") (pintype "power_in"))
      (node (ref "U1") (pin "N12") (pinfunction "VCC_N12") (pintype "power_in"))
      (node (ref "U1") (pin "N14") (pinfunction "VCC_N14") (pintype "power_in"))
      (node (ref "U1") (pin "N5") (pinfunction "VCC_N5") (pintype "power_in"))
      (node (ref "U1") (pin "N9") (pinfunction "VCC_N9") (pintype "power_in"))
      (node (ref "U1") (pin "P11") (pinfunction "VCC_P11") (pintype "power_in"))
      (node (ref "U1") (pin "P13") (pinfunction "VCC_P13") (pintype "power_in"))
      (node (ref "U1") (pin "P14") (pinfunction "VCC_P14") (pintype "power_in"))
      (node (ref "U1") (pin "P15") (pinfunction "VCC_P15") (pintype "power_in"))
      (node (ref "U1") (pin "R10") (pinfunction "VCC_R10") (pintype "power_in"))
      (node (ref "U1") (pin "R12") (pinfunction "VCC_R12") (pintype "power_in"))
      (node (ref "U1") (pin "R14") (pinfunction "VCC_R14") (pintype "power_in"))
      (node (ref "U1") (pin "R5") (pinfunction "VCC_R5") (pintype "power_in"))
      (node (ref "U1") (pin "R9") (pinfunction "VCC_R9") (pintype "power_in"))
      (node (ref "U1") (pin "T15") (pinfunction "VCC_T15") (pintype "power_in"))
      (node (ref "U1") (pin "T4") (pinfunction "VCC_T4") (pintype "power_in"))
      (node (ref "U1") (pin "T5") (pinfunction "VCC_T5") (pintype "power_in"))
      (node (ref "U1") (pin "T9") (pinfunction "VCC_T9") (pintype "power_in"))
      (node (ref "U1") (pin "U26") (pinfunction "VCC_U26") (pintype "power_in"))
    )
    (net (code "66") (name "VCCIO3A") (class "Default")
      (node (ref "U1") (pin "AA5") (pinfunction "VCCIO3A_AA5") (pintype "power_in"))
      (node (ref "U1") (pin "W9") (pinfunction "VCCIO3A_W9") (pintype "power_in"))
    )
    (net (code "67") (name "VCCIO3B") (class "Default")
      (node (ref "U1") (pin "AA12") (pinfunction "VCCIO3B_AA12") (pintype "power_in"))
      (node (ref "U1") (pin "AE10") (pinfunction "VCCIO3B_AE10") (pintype "power_in"))
      (node (ref "U1") (pin "AE13") (pinfunction "VCCIO3B_AE13") (pintype "power_in"))
      (node (ref "U1") (pin "AG4") (pinfunction "VCCIO3B_AG4") (pintype "power_in"))
    )
    (net (code "68") (name "VCCIO4A") (class "Default")
      (node (ref "U1") (pin "AA16") (pinfunction "VCCIO4A_AA16") (pintype "power_in"))
      (node (ref "U1") (pin "AE21") (pinfunction "VCCIO4A_AE21") (pintype "power_in"))
      (node (ref "U1") (pin "AF14") (pinfunction "VCCIO4A_AF14") (pintype "power_in"))
      (node (ref "U1") (pin "AF19") (pinfunction "VCCIO4A_AF19") (pintype "power_in"))
      (node (ref "U1") (pin "AG12") (pinfunction "VCCIO4A_AG12") (pintype "power_in"))
      (node (ref "U1") (pin "AG22") (pinfunction "VCCIO4A_AG22") (pintype "power_in"))
      (node (ref "U1") (pin "AH15") (pinfunction "VCCIO4A_AH15") (pintype "power_in"))
      (node (ref "U1") (pin "AH25") (pinfunction "VCCIO4A_AH25") (pintype "power_in"))
      (node (ref "U1") (pin "W13") (pinfunction "VCCIO4A_W13") (pintype "power_in"))
    )
    (net (code "69") (name "VCCIO5A") (class "Default")
      (node (ref "U1") (pin "AC25") (pinfunction "VCCIO5A_AC25") (pintype "power_in"))
      (node (ref "U1") (pin "W17") (pinfunction "VCCIO5A_W17") (pintype "power_in"))
    )
    (net (code "70") (name "VCCIO5B") (class "Default")
      (node (ref "U1") (pin "W25") (pinfunction "VCCIO5B_W25") (pintype "power_in"))
    )
    (net (code "71") (name "VCCIO8A") (class "Default")
      (node (ref "U1") (pin "E7") (pinfunction "VCCIO8A_E7") (pintype "power_in"))
    )
    (net (code "72") (name "VCC_AUX") (class "Default")
      (node (ref "L5") (pin "1") (pinfunction "1_1") (pintype "passive"))
      (node (ref "U1") (pin "AC21") (pinfunction "VCC_AUX_AC21") (pintype "power_in"))
      (node (ref "U1") (pin "AC8") (pinfunction "VCC_AUX_AC8") (pintype "power_in"))
      (node (ref "U1") (pin "AD15") (pinfunction "VCC_AUX_AD15") (pintype "power_in"))
      (node (ref "U1") (pin "E15") (pinfunction "VCC_AUX_E15") (pintype "power_in"))
      (node (ref "U1") (pin "F8") (pinfunction "VCC_AUX_F8") (pintype "power_in"))
      (node (ref "U1") (pin "H23") (pinfunction "VCCPLL_HPS_H23") (pintype "power_in"))
    )
    (net (code "73") (name "VCC_AUX_SHARED") (class "Default")
      (node (ref "L7") (pin "1") (pinfunction "1_1") (pintype "passive"))
      (node (ref "U1") (pin "F21") (pinfunction "VCC_AUX_SHARED_F21") (pintype "power_in"))
    )
    (net (code "74") (name "VCC_BAT") (class "Default")
      (node (ref "L8") (pin "1") (pinfunction "1_1") (pintype "passive"))
      (node (ref "U1") (pin "D7") (pinfunction "VCCBAT_D7") (pintype "power_in"))
    )
    (net (code "75") (name "unconnected-(SW5-Pad7)") (class "Default")
      (node (ref "SW5") (pin "7") (pinfunction "7_7") (pintype "passive+no_connect"))
    )
    (net (code "76") (name "unconnected-(U1J-SDMMC_D4,_(_,__,__,__,__,__,_SDMMC_D4,_USB0_D4,__,_HPS_GPIO40)-PadH13)") (class "Default")
      (node (ref "U1") (pin "H13") (pinfunction "SDMMC_D4,_(_,__,__,__,__,__,_SDMMC_D4,_USB0_D4,__,_HPS_GPIO40)_H13") (pintype "bidirectional+no_connect"))
    )
    (net (code "77") (name "unconnected-(U1J-SDMMC_D5,_(_,__,__,__,__,__,_SDMMC_D5,_USB0_D5,__,_HPS_GPIO41)-PadA4)") (class "Default")
      (node (ref "U1") (pin "A4") (pinfunction "SDMMC_D5,_(_,__,__,__,__,__,_SDMMC_D5,_USB0_D5,__,_HPS_GPIO41)_A4") (pintype "bidirectional+no_connect"))
    )
    (net (code "78") (name "unconnected-(U1J-SDMMC_FB_CLK_IN,_(_,__,__,__,__,__,_SDMMC_FB_CLK_IN,_USB0_CLK,__,_HPS_GPIO44)-PadB12)") (class "Default")
      (node (ref "U1") (pin "B12") (pinfunction "SDMMC_FB_CLK_IN,_(_,__,__,__,__,__,_SDMMC_FB_CLK_IN,_USB0_CLK,__,_HPS_GPIO44)_B12") (pintype "bidirectional+no_connect"))
    )
    (net (code "79") (name "unconnected-(U1J-SDMMC_PWREN,_(_,__,__,__,__,__,_SDMMC_PWREN,_USB0_D1,__,_HPS_GPIO37)-PadA5)") (class "Default")
      (node (ref "U1") (pin "A5") (pinfunction "SDMMC_PWREN,_(_,__,__,__,__,__,_SDMMC_PWREN,_USB0_D1,__,_HPS_GPIO37)_A5") (pintype "bidirectional+no_connect"))
    )
    (net (code "80") (name "unconnected-(U1M-HPS_GPI0-PadM25)") (class "Default")
      (node (ref "U1") (pin "M25") (pinfunction "HPS_GPI0_M25") (pintype "input+no_connect"))
    )
    (net (code "81") (name "unconnected-(U1M-HPS_GPI1-PadK27)") (class "Default")
      (node (ref "U1") (pin "K27") (pinfunction "HPS_GPI1_K27") (pintype "input+no_connect"))
    )
    (net (code "82") (name "unconnected-(U1M-HPS_GPI2-PadR20)") (class "Default")
      (node (ref "U1") (pin "R20") (pinfunction "HPS_GPI2_R20") (pintype "input+no_connect"))
    )
    (net (code "83") (name "unconnected-(U1M-HPS_GPI3-PadR21)") (class "Default")
      (node (ref "U1") (pin "R21") (pinfunction "HPS_GPI3_R21") (pintype "input+no_connect"))
    )
    (net (code "84") (name "unconnected-(U1M-HPS_GPI4-PadR28)") (class "Default")
      (node (ref "U1") (pin "R28") (pinfunction "HPS_GPI4_R28") (pintype "input+no_connect"))
    )
    (net (code "85") (name "unconnected-(U1M-HPS_GPI5-PadP26)") (class "Default")
      (node (ref "U1") (pin "P26") (pinfunction "HPS_GPI5_P26") (pintype "input+no_connect"))
    )
    (net (code "86") (name "unconnected-(U1M-HPS_GPI6-PadT17)") (class "Default")
      (node (ref "U1") (pin "T17") (pinfunction "HPS_GPI6_T17") (pintype "input+no_connect"))
    )
    (net (code "87") (name "unconnected-(U1M-HPS_GPI7-PadT16)") (class "Default")
      (node (ref "U1") (pin "T16") (pinfunction "HPS_GPI7_T16") (pintype "input+no_connect"))
    )
    (net (code "88") (name "unconnected-(U1M-HPS_GPI8-PadY28)") (class "Default")
      (node (ref "U1") (pin "Y28") (pinfunction "HPS_GPI8_Y28") (pintype "input+no_connect"))
    )
    (net (code "89") (name "unconnected-(U1M-HPS_GPI9-PadY26)") (class "Default")
      (node (ref "U1") (pin "Y26") (pinfunction "HPS_GPI9_Y26") (pintype "input+no_connect"))
    )
    (net (code "90") (name "unconnected-(U1M-HPS_GPI10-PadU15)") (class "Default")
      (node (ref "U1") (pin "U15") (pinfunction "HPS_GPI10_U15") (pintype "input+no_connect"))
    )
    (net (code "91") (name "unconnected-(U1M-HPS_GPI11-PadU16)") (class "Default")
      (node (ref "U1") (pin "U16") (pinfunction "HPS_GPI11_U16") (pintype "input+no_connect"))
    )
    (net (code "92") (name "unconnected-(U1M-HPS_GPI12-PadAC27)") (class "Default")
      (node (ref "U1") (pin "AC27") (pinfunction "HPS_GPI12_AC27") (pintype "input+no_connect"))
    )
    (net (code "93") (name "unconnected-(U1M-HPS_GPI13-PadV24)") (class "Default")
      (node (ref "U1") (pin "V24") (pinfunction "HPS_GPI13_V24") (pintype "input+no_connect"))
    )
    (net (code "94") (name "unconnected-(U1U-DNU-PadA2)") (class "Default")
      (node (ref "U1") (pin "A2") (pinfunction "DNU_A2") (pintype "passive+no_connect"))
    )
    (net (code "95") (name "unconnected-(U1U-DNU-PadAD1)") (class "Default")
      (node (ref "U1") (pin "AD1") (pinfunction "DNU_AD1") (pintype "passive+no_connect"))
    )
    (net (code "96") (name "unconnected-(U1U-DNU-PadAD2)") (class "Default")
      (node (ref "U1") (pin "AD2") (pinfunction "DNU_AD2") (pintype "passive+no_connect"))
    )
    (net (code "97") (name "unconnected-(U1U-DNU-PadAE14)") (class "Default")
      (node (ref "U1") (pin "AE14") (pinfunction "DNU_AE14") (pintype "passive+no_connect"))
    )
    (net (code "98") (name "unconnected-(U1U-DNU-PadB2)") (class "Default")
      (node (ref "U1") (pin "B2") (pinfunction "DNU_B2") (pintype "passive+no_connect"))
    )
    (net (code "99") (name "unconnected-(U1U-DNU-PadD1)") (class "Default")
      (node (ref "U1") (pin "D1") (pinfunction "DNU_D1") (pintype "passive+no_connect"))
    )
    (net (code "100") (name "unconnected-(U1U-DNU-PadD2)") (class "Default")
      (node (ref "U1") (pin "D2") (pinfunction "DNU_D2") (pintype "passive+no_connect"))
    )
    (net (code "101") (name "unconnected-(U1U-DNU-PadD23)") (class "Default")
      (node (ref "U1") (pin "D23") (pinfunction "DNU_D23") (pintype "passive+no_connect"))
    )
    (net (code "102") (name "unconnected-(U1U-DNU-PadE12)") (class "Default")
      (node (ref "U1") (pin "E12") (pinfunction "DNU_E12") (pintype "passive+no_connect"))
    )
    (net (code "103") (name "unconnected-(U1U-DNU-PadH1)") (class "Default")
      (node (ref "U1") (pin "H1") (pinfunction "DNU_H1") (pintype "passive+no_connect"))
    )
    (net (code "104") (name "unconnected-(U1U-DNU-PadH2)") (class "Default")
      (node (ref "U1") (pin "H2") (pinfunction "DNU_H2") (pintype "passive+no_connect"))
    )
    (net (code "105") (name "unconnected-(U1U-DNU-PadM1)") (class "Default")
      (node (ref "U1") (pin "M1") (pinfunction "DNU_M1") (pintype "passive+no_connect"))
    )
    (net (code "106") (name "unconnected-(U1U-DNU-PadM2)") (class "Default")
      (node (ref "U1") (pin "M2") (pinfunction "DNU_M2") (pintype "passive+no_connect"))
    )
    (net (code "107") (name "unconnected-(U1U-DNU-PadT1)") (class "Default")
      (node (ref "U1") (pin "T1") (pinfunction "DNU_T1") (pintype "passive+no_connect"))
    )
    (net (code "108") (name "unconnected-(U1U-DNU-PadT2)") (class "Default")
      (node (ref "U1") (pin "T2") (pinfunction "DNU_T2") (pintype "passive+no_connect"))
    )
    (net (code "109") (name "unconnected-(U1U-DNU-PadU8)") (class "Default")
      (node (ref "U1") (pin "U8") (pinfunction "DNU_U8") (pintype "passive+no_connect"))
    )
    (net (code "110") (name "unconnected-(U1U-DNU-PadY1)") (class "Default")
      (node (ref "U1") (pin "Y1") (pinfunction "DNU_Y1") (pintype "passive+no_connect"))
    )
    (net (code "111") (name "unconnected-(U1U-DNU-PadY2)") (class "Default")
      (node (ref "U1") (pin "Y2") (pinfunction "DNU_Y2") (pintype "passive+no_connect"))
    )
  )
)
